# AutoRange.net
KiCad netlist of a schematic drawn in Altium Designer
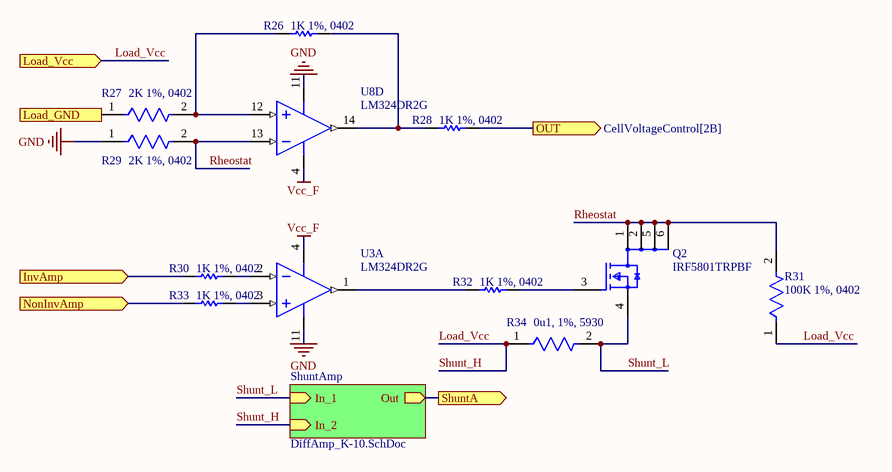
[diagram p0: AutoRange.SchDoc]

(export (version "E")
  (design (tool "Eeschema 10.0.6"))
  (components
    (comp (ref "Q2")
      (value "IRF5801TRPBF")
      (footprint "FP-PG-TSOP-6-MFG")
      (description "MOSFET N-CH 200V 600MA MICRO6")
      (libsource (lib "Altium Content Vault") (part "f60611ca5ac0ac653dab7e7b80e546e"))
    )
    (comp (ref "R26")
      (value "1K 1%, 0402")
      (footprint "RESC1005X40X25NL05T05")
      (description "Chip Resistor, 1 KOhm, +/- 1%, 100 mW, -55 to 155 degC, 0402 (1005 Metric), RoHS, Tape and Reel")
      (fields (field (name "PARTNUMBER") "ERJ-2RKF1001X") (field (name "MANUFACTURER") "Basic Passives"))
      (libsource (lib "Altium Content Vault") (part "RES-2"))
    )
    (comp (ref "R27")
      (value "2K 1%, 0402")
      (footprint "FP-ERJ2RK-MFG")
      (description "RES SMD 2K OHM 1% 1/10W 0402")
      (fields (field (name "TOLERANCE") "1%"))
      (libsource (lib "Altium Content Vault") (part "1029c3af85768c4190bb7ad29bc67b5"))
    )
    (comp (ref "R28")
      (value "1K 1%, 0402")
      (footprint "RESC1005X40X25NL05T05")
      (description "Chip Resistor, 1 KOhm, +/- 1%, 100 mW, -55 to 155 degC, 0402 (1005 Metric), RoHS, Tape and Reel")
      (fields (field (name "PARTNUMBER") "ERJ-2RKF1001X") (field (name "MANUFACTURER") "Basic Passives"))
      (libsource (lib "Altium Content Vault") (part "RES-2"))
    )
    (comp (ref "R29")
      (value "2K 1%, 0402")
      (footprint "FP-ERJ2RK-MFG")
      (description "RES SMD 2K OHM 1% 1/10W 0402")
      (fields (field (name "TOLERANCE") "1%"))
      (libsource (lib "Altium Content Vault") (part "1029c3af85768c4190bb7ad29bc67b5"))
    )
    (comp (ref "R30")
      (value "1K 1%, 0402")
      (footprint "RESC1005X40X25NL05T05")
      (description "Chip Resistor, 1 KOhm, +/- 1%, 100 mW, -55 to 155 degC, 0402 (1005 Metric), RoHS, Tape and Reel")
      (fields (field (name "PARTNUMBER") "ERJ-2RKF1001X") (field (name "MANUFACTURER") "Basic Passives"))
      (libsource (lib "Altium Content Vault") (part "RES-2"))
    )
    (comp (ref "R31")
      (value "100K 1%, 0402")
      (footprint "FP-ERJ2RK-IPC_C")
      (description "RES SMD 100K OHM 1% 1/10W 0402")
      (fields (field (name "TOLERANCE") "1%"))
      (libsource (lib "Altium Content Vault") (part "1029c3af85768c4190bb7ad29bc67b5"))
    )
    (comp (ref "R32")
      (value "1K 1%, 0402")
      (footprint "RESC1005X40X25NL05T05")
      (description "Chip Resistor, 1 KOhm, +/- 1%, 100 mW, -55 to 155 degC, 0402 (1005 Metric), RoHS, Tape and Reel")
      (fields (field (name "PARTNUMBER") "ERJ-2RKF1001X") (field (name "MANUFACTURER") "Basic Passives"))
      (libsource (lib "Altium Content Vault") (part "RES-2"))
    )
    (comp (ref "R33")
      (value "1K 1%, 0402")
      (footprint "RESC1005X40X25NL05T05")
      (description "Chip Resistor, 1 KOhm, +/- 1%, 100 mW, -55 to 155 degC, 0402 (1005 Metric), RoHS, Tape and Reel")
      (fields (field (name "PARTNUMBER") "ERJ-2RKF1001X") (field (name "MANUFACTURER") "Basic Passives"))
      (libsource (lib "Altium Content Vault") (part "RES-2"))
    )
    (comp (ref "R34")
      (value "0u1, 1%, 5930")
      (footprint "FP-CSS2H-5930K-1L00F-MFG")
      (description "CSS2H-5930K-1L00F Res Metal Strip 5930 0.001 Ohm 1% 9W ±50ppm/C Pad SMD Automotive T/R")
      (fields (field (name "TOLERANCE") "1%"))
      (libsource (lib "Altium Content Vault") (part "1029c3af85768c4190bb7ad29bc67b5"))
    )
    (comp (ref "U3")
      (value "LM324DR2G")
      (footprint "ONSC-SOIC-14-751A-03_V")
      (fields (field (name "MANUFACTURER") "On Semiconductor"))
      (libsource (lib "Altium Content Vault") (part "ONSC-LM224_324_2902_NCV2902-14"))
    )
    (comp (ref "U8")
      (value "LM324DR2G")
      (footprint "ONSC-SOIC-14-751A-03_V")
      (fields (field (name "MANUFACTURER") "On Semiconductor"))
      (libsource (lib "Altium Content Vault") (part "ONSC-LM224_324_2902_NCV2902-14"))
    )
  )
  (nets
    (net (code "1") (name "/InvAmp") (class "Default")
      (node (ref "R30") (pin "1") (pinfunction "1_1") (pintype "passive"))
    )
    (net (code "2") (name "/Load_GND") (class "Default")
      (node (ref "R27") (pin "1") (pinfunction "1_1") (pintype "passive"))
    )
    (net (code "3") (name "/Load_Vcc") (class "Default")
      (node (ref "R31") (pin "1") (pinfunction "1_1") (pintype "passive"))
      (node (ref "R34") (pin "1") (pinfunction "1_1") (pintype "passive"))
    )
    (net (code "4") (name "/NonInvAmp") (class "Default")
      (node (ref "R33") (pin "1") (pinfunction "1_1") (pintype "passive"))
    )
    (net (code "5") (name "/OUT") (class "Default")
      (node (ref "R28") (pin "2") (pinfunction "2_2") (pintype "passive"))
    )
    (net (code "6") (name "/Rheostat") (class "Default")
      (node (ref "Q2") (pin "1") (pinfunction "D_1") (pintype "passive"))
      (node (ref "Q2") (pin "2") (pinfunction "D_2") (pintype "passive"))
      (node (ref "Q2") (pin "5") (pinfunction "D_5") (pintype "passive"))
      (node (ref "Q2") (pin "6") (pinfunction "D_6") (pintype "passive"))
      (node (ref "R29") (pin "2") (pinfunction "2_2") (pintype "passive"))
      (node (ref "R31") (pin "2") (pinfunction "2_2") (pintype "passive"))
      (node (ref "U8") (pin "13") (pinfunction "IN4-_13") (pintype "input"))
    )
    (net (code "8") (name "/Shunt_L") (class "Default")
      (node (ref "Q2") (pin "4") (pinfunction "S_4") (pintype "passive"))
      (node (ref "R34") (pin "2") (pinfunction "2_2") (pintype "passive"))
    )
    (net (code "9") (name "GND") (class "Default")
      (node (ref "R29") (pin "1") (pinfunction "1_1") (pintype "passive"))
      (node (ref "U3") (pin "11") (pinfunction "VEE/GND_11") (pintype "power_in"))
      (node (ref "U8") (pin "11") (pinfunction "VEE/GND_11") (pintype "power_in"))
    )
    (net (code "10") (name "Net-(Q2-G)") (class "Default")
      (node (ref "Q2") (pin "3") (pinfunction "G_3") (pintype "passive"))
      (node (ref "R32") (pin "2") (pinfunction "2_2") (pintype "passive"))
    )
    (net (code "11") (name "Net-(U3A-IN1+)") (class "Default")
      (node (ref "R33") (pin "2") (pinfunction "2_2") (pintype "passive"))
      (node (ref "U3") (pin "3") (pinfunction "IN1+_3") (pintype "input"))
    )
    (net (code "12") (name "Net-(U3A-IN1-)") (class "Default")
      (node (ref "R30") (pin "2") (pinfunction "2_2") (pintype "passive"))
      (node (ref "U3") (pin "2") (pinfunction "IN1-_2") (pintype "input"))
    )
    (net (code "13") (name "Net-(U3A-OUT1)") (class "Default")
      (node (ref "R32") (pin "1") (pinfunction "1_1") (pintype "passive"))
      (node (ref "U3") (pin "1") (pinfunction "OUT1_1") (pintype "output"))
    )
    (net (code "14") (name "Net-(U8D-IN4+)") (class "Default")
      (node (ref "R26") (pin "1") (pinfunction "1_1") (pintype "passive"))
      (node (ref "R27") (pin "2") (pinfunction "2_2") (pintype "passive"))
      (node (ref "U8") (pin "12") (pinfunction "IN4+_12") (pintype "input"))
    )
    (net (code "15") (name "Net-(U8D-OUT4)") (class "Default")
      (node (ref "R26") (pin "2") (pinfunction "2_2") (pintype "passive"))
      (node (ref "R28") (pin "1") (pinfunction "1_1") (pintype "passive"))
      (node (ref "U8") (pin "14") (pinfunction "OUT4_14") (pintype "output"))
    )
    (net (code "16") (name "Vcc_F") (class "Default")
      (node (ref "U3") (pin "4") (pinfunction "VCC_4") (pintype "power_in"))
      (node (ref "U8") (pin "4") (pinfunction "VCC_4") (pintype "power_in"))
    )
  )
)
